# PIC_16F877A_Board_V4_2_SMD.net
KiCad netlist of a schematic drawn in EAGLE
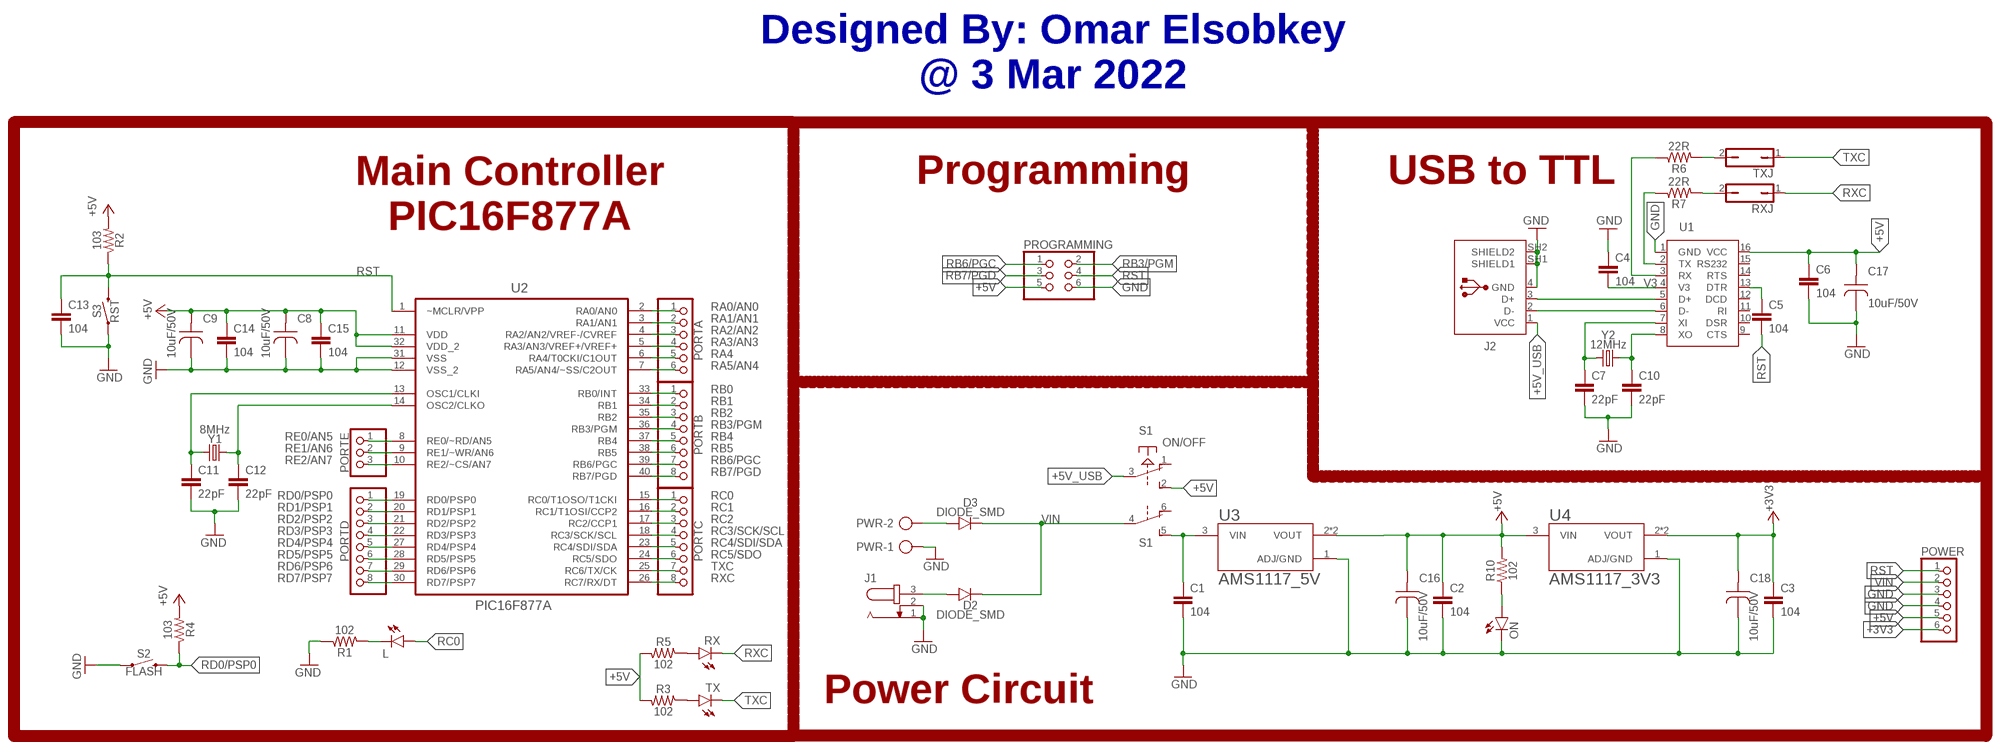
[diagram p0: schematic, sheet 1]

(export (version "E")
  (design (tool "Eeschema 10.0.6"))
  (components
    (comp (ref "C1")
      (value "104")
      (footprint "eagle-import:C0805K")
      (libsource (lib "eagle-import") (part "C-EUC0805K"))
    )
    (comp (ref "C2")
      (value "104")
      (footprint "eagle-import:C0805K")
      (libsource (lib "eagle-import") (part "C-EUC0805K"))
    )
    (comp (ref "C3")
      (value "104")
      (footprint "eagle-import:C0805K")
      (libsource (lib "eagle-import") (part "C-EUC0805K"))
    )
    (comp (ref "C4")
      (value "104")
      (footprint "eagle-import:C0805K")
      (libsource (lib "eagle-import") (part "C-EUC0805K"))
    )
    (comp (ref "C5")
      (value "104")
      (footprint "eagle-import:C0805K")
      (libsource (lib "eagle-import") (part "C-EUC0805K"))
    )
    (comp (ref "C6")
      (value "104")
      (footprint "eagle-import:C0805K")
      (libsource (lib "eagle-import") (part "C-EUC0805K"))
    )
    (comp (ref "C7")
      (value "22pF")
      (footprint "eagle-import:C0805K")
      (libsource (lib "eagle-import") (part "C-EUC0805K"))
    )
    (comp (ref "C8")
      (value "10uF/50V")
      (footprint "eagle-import:D5")
      (libsource (lib "eagle-import") (part "10UF/50V"))
    )
    (comp (ref "C9")
      (value "10uF/50V")
      (footprint "eagle-import:D5")
      (libsource (lib "eagle-import") (part "10UF/50V"))
    )
    (comp (ref "C10")
      (value "22pF")
      (footprint "eagle-import:C0805K")
      (libsource (lib "eagle-import") (part "C-EUC0805K"))
    )
    (comp (ref "C11")
      (value "22pF")
      (footprint "eagle-import:C0805K")
      (libsource (lib "eagle-import") (part "C-EUC0805K"))
    )
    (comp (ref "C12")
      (value "22pF")
      (footprint "eagle-import:C0805K")
      (libsource (lib "eagle-import") (part "C-EUC0805K"))
    )
    (comp (ref "C13")
      (value "104")
      (footprint "eagle-import:C0805K")
      (libsource (lib "eagle-import") (part "C-EUC0805K"))
    )
    (comp (ref "C14")
      (value "104")
      (footprint "eagle-import:C0805K")
      (libsource (lib "eagle-import") (part "C-EUC0805K"))
    )
    (comp (ref "C15")
      (value "104")
      (footprint "eagle-import:C0805K")
      (libsource (lib "eagle-import") (part "C-EUC0805K"))
    )
    (comp (ref "C16")
      (value "10uF/50V")
      (footprint "eagle-import:D5")
      (libsource (lib "eagle-import") (part "10UF/50V"))
    )
    (comp (ref "C17")
      (value "10uF/50V")
      (footprint "eagle-import:D5")
      (libsource (lib "eagle-import") (part "10UF/50V"))
    )
    (comp (ref "C18")
      (value "10uF/50V")
      (footprint "eagle-import:D5")
      (libsource (lib "eagle-import") (part "10UF/50V"))
    )
    (comp (ref "D2")
      (value "DIODE_SMD")
      (footprint "eagle-import:SMA_DO-214AC")
      (fields (field (name "MF") "NKK Switches") (field (name "MP") "S1A"))
      (libsource (lib "eagle-import") (part "DIODE_SMD"))
    )
    (comp (ref "D3")
      (value "DIODE_SMD")
      (footprint "eagle-import:SMA_DO-214AC")
      (fields (field (name "MF") "NKK Switches") (field (name "MP") "S1A"))
      (libsource (lib "eagle-import") (part "DIODE_SMD"))
    )
    (comp (ref "J1")
      (value "JACK-PLUG0")
      (footprint "eagle-import:SPC4077")
      (libsource (lib "eagle-import") (part "JACK-PLUG0"))
    )
    (comp (ref "J2")
      (value "61729-1011")
      (footprint "eagle-import:61729-1011BLF")
      (fields (field (name "MANUFACTURER") "Amphenol ICC (FCI)") (field (name "MPN") "61729-1011BLF"))
      (libsource (lib "eagle-import") (part "61729-1011"))
    )
    (comp (ref "L")
      (value "LEDCHIPLED_1206")
      (footprint "eagle-import:CHIPLED_1206")
      (libsource (lib "eagle-import") (part "LEDCHIPLED_1206"))
    )
    (comp (ref "ON")
      (value "LEDCHIPLED_1206")
      (footprint "eagle-import:CHIPLED_1206")
      (libsource (lib "eagle-import") (part "LEDCHIPLED_1206"))
    )
    (comp (ref "PORTA")
      (value "PINHD-1X6")
      (footprint "eagle-import:1X06")
      (libsource (lib "eagle-import") (part "PINHD-1X6"))
    )
    (comp (ref "PORTB")
      (value "PINHD-1X8")
      (footprint "eagle-import:1X08")
      (libsource (lib "eagle-import") (part "PINHD-1X8"))
    )
    (comp (ref "PORTC")
      (value "PINHD-1X8")
      (footprint "eagle-import:1X08")
      (libsource (lib "eagle-import") (part "PINHD-1X8"))
    )
    (comp (ref "PORTD")
      (value "PINHD-1X8")
      (footprint "eagle-import:1X08")
      (libsource (lib "eagle-import") (part "PINHD-1X8"))
    )
    (comp (ref "PORTE")
      (value "PINHD-1X3")
      (footprint "eagle-import:1X03")
      (libsource (lib "eagle-import") (part "PINHD-1X3"))
    )
    (comp (ref "POWER")
      (value "PINHD-1X6")
      (footprint "eagle-import:1X06")
      (libsource (lib "eagle-import") (part "PINHD-1X6"))
    )
    (comp (ref "PROGRAMMING")
      (value "PINHD-2X3")
      (footprint "eagle-import:2X03")
      (libsource (lib "eagle-import") (part "PINHD-2X3"))
    )
    (comp (ref "PWR") (value "2P") (footprint "eagle-import:2P") (libsource (lib "eagle-import") (part "2P")))
    (comp (ref "R1")
      (value "102")
      (footprint "eagle-import:1206")
      (libsource (lib "eagle-import") (part "RESISTOR1206"))
    )
    (comp (ref "R2")
      (value "103")
      (footprint "eagle-import:1206")
      (libsource (lib "eagle-import") (part "RESISTOR1206"))
    )
    (comp (ref "R3")
      (value "102")
      (footprint "eagle-import:1206")
      (libsource (lib "eagle-import") (part "RESISTOR1206"))
    )
    (comp (ref "R4")
      (value "103")
      (footprint "eagle-import:1206")
      (libsource (lib "eagle-import") (part "RESISTOR1206"))
    )
    (comp (ref "R5")
      (value "102")
      (footprint "eagle-import:1206")
      (libsource (lib "eagle-import") (part "RESISTOR1206"))
    )
    (comp (ref "R6")
      (value "22R")
      (footprint "eagle-import:1206")
      (libsource (lib "eagle-import") (part "RESISTOR1206"))
    )
    (comp (ref "R7")
      (value "22R")
      (footprint "eagle-import:1206")
      (libsource (lib "eagle-import") (part "RESISTOR1206"))
    )
    (comp (ref "R10")
      (value "102")
      (footprint "eagle-import:1206")
      (libsource (lib "eagle-import") (part "RESISTOR1206"))
    )
    (comp (ref "RX")
      (value "LEDCHIPLED_1206")
      (footprint "eagle-import:CHIPLED_1206")
      (libsource (lib "eagle-import") (part "LEDCHIPLED_1206"))
    )
    (comp (ref "RXJ")
      (value "JP1Q")
      (footprint "eagle-import:JP1")
      (libsource (lib "eagle-import") (part "JP1Q"))
    )
    (comp (ref "S1")
      (value "ON/OFF")
      (footprint "eagle-import:PVA2R")
      (libsource (lib "eagle-import") (part "PVA2R"))
    )
    (comp (ref "S2")
      (value "FLASH")
      (footprint "eagle-import:TACTILE_SWITCH_SMD_6.0X3.5MM")
      (libsource (lib "eagle-import") (part "MOMENTARY-SWITCH-SPST-SMD-6.0X3.5MM"))
    )
    (comp (ref "S3")
      (value "RST")
      (footprint "eagle-import:TACTILE_SWITCH_SMD_6.0X3.5MM")
      (libsource (lib "eagle-import") (part "MOMENTARY-SWITCH-SPST-SMD-6.0X3.5MM"))
    )
    (comp (ref "TX")
      (value "LEDCHIPLED_1206")
      (footprint "eagle-import:CHIPLED_1206")
      (libsource (lib "eagle-import") (part "LEDCHIPLED_1206"))
    )
    (comp (ref "TXJ")
      (value "JP1Q")
      (footprint "eagle-import:JP1")
      (libsource (lib "eagle-import") (part "JP1Q"))
    )
    (comp (ref "U1")
      (value "CH340G")
      (footprint "eagle-import:SOP-16")
      (libsource (lib "eagle-import") (part "CH340G"))
    )
    (comp (ref "U2")
      (value "PIC16F877A")
      (footprint "eagle-import:PDIP-40")
      (fields (field (name "MF") "Microchip") (field (name "MP") "PIC16F877A-I/P"))
      (libsource (lib "eagle-import") (part "PIC16F877A-I/P"))
    )
    (comp (ref "U3")
      (value "AMS1117_5V")
      (footprint "eagle-import:SOT223")
      (libsource (lib "eagle-import") (part "AMS1117"))
    )
    (comp (ref "U4")
      (value "AMS1117_3V3")
      (footprint "eagle-import:SOT223")
      (libsource (lib "eagle-import") (part "AMS1117"))
    )
    (comp (ref "Y1")
      (value "8MHz")
      (footprint "eagle-import:HC49U")
      (libsource (lib "eagle-import") (part "CRYSTALPTH-HC49UV"))
    )
    (comp (ref "Y2")
      (value "12MHz")
      (footprint "eagle-import:HC49U")
      (libsource (lib "eagle-import") (part "CRYSTALPTH-HC49UV"))
    )
  )
  (nets
    (net (code "1") (name "+3V3") (class "Default")
      (node (ref "C18") (pin "A") (pinfunction "A_A") (pintype "bidirectional"))
      (node (ref "C3") (pin "1") (pinfunction "1_1") (pintype "passive"))
      (node (ref "POWER") (pin "6") (pinfunction "6_6") (pintype "passive"))
      (node (ref "U4") (pin "2") (pinfunction "VOUT_2") (pintype "output"))
      (node (ref "U4") (pin "4") (pinfunction "VOUT_4") (pintype "output"))
    )
    (net (code "2") (name "+5V") (class "Default")
      (node (ref "C14") (pin "1") (pinfunction "1_1") (pintype "passive"))
      (node (ref "C15") (pin "1") (pinfunction "1_1") (pintype "passive"))
      (node (ref "C16") (pin "A") (pinfunction "A_A") (pintype "bidirectional"))
      (node (ref "C17") (pin "A") (pinfunction "A_A") (pintype "bidirectional"))
      (node (ref "C2") (pin "1") (pinfunction "1_1") (pintype "passive"))
      (node (ref "C6") (pin "1") (pinfunction "1_1") (pintype "passive"))
      (node (ref "C8") (pin "A") (pinfunction "A_A") (pintype "bidirectional"))
      (node (ref "C9") (pin "A") (pinfunction "A_A") (pintype "bidirectional"))
      (node (ref "POWER") (pin "5") (pinfunction "5_5") (pintype "passive"))
      (node (ref "PROGRAMMING") (pin "5") (pinfunction "5_5") (pintype "passive"))
      (node (ref "R10") (pin "2") (pinfunction "2_2") (pintype "passive"))
      (node (ref "R2") (pin "2") (pinfunction "2_2") (pintype "passive"))
      (node (ref "R3") (pin "2") (pinfunction "2_2") (pintype "passive"))
      (node (ref "R4") (pin "2") (pinfunction "2_2") (pintype "passive"))
      (node (ref "R5") (pin "2") (pinfunction "2_2") (pintype "passive"))
      (node (ref "S1") (pin "2") (pinfunction "S_2") (pintype "passive"))
      (node (ref "U1") (pin "16") (pinfunction "VCC_16") (pintype "bidirectional"))
      (node (ref "U2") (pin "11") (pinfunction "VDD_11") (pintype "power_in"))
      (node (ref "U2") (pin "32") (pinfunction "VDD_2_32") (pintype "power_in"))
      (node (ref "U3") (pin "2") (pinfunction "VOUT_2") (pintype "output"))
      (node (ref "U3") (pin "4") (pinfunction "VOUT_4") (pintype "output"))
      (node (ref "U4") (pin "3") (pinfunction "VIN_3") (pintype "input"))
    )
    (net (code "3") (name "+5V_USB") (class "Default")
      (node (ref "J2") (pin "1") (pinfunction "VCC_1") (pintype "power_in"))
      (node (ref "S1") (pin "3") (pinfunction "P_3") (pintype "passive"))
    )
    (net (code "4") (name "/RA0{slash}AN0") (class "Default")
      (node (ref "PORTA") (pin "1") (pinfunction "1_1") (pintype "passive"))
      (node (ref "U2") (pin "2") (pinfunction "RA0/AN0_2") (pintype "bidirectional"))
    )
    (net (code "5") (name "/RA1{slash}AN1") (class "Default")
      (node (ref "PORTA") (pin "2") (pinfunction "2_2") (pintype "passive"))
      (node (ref "U2") (pin "3") (pinfunction "RA1/AN1_3") (pintype "bidirectional"))
    )
    (net (code "6") (name "/RA2{slash}AN2") (class "Default")
      (node (ref "PORTA") (pin "3") (pinfunction "3_3") (pintype "passive"))
      (node (ref "U2") (pin "4") (pinfunction "RA2/AN2/VREF-/CVREF_4") (pintype "bidirectional"))
    )
    (net (code "7") (name "/RA3{slash}AN3") (class "Default")
      (node (ref "PORTA") (pin "4") (pinfunction "4_4") (pintype "passive"))
      (node (ref "U2") (pin "5") (pinfunction "RA3/AN3/VREF+/VREF+_5") (pintype "bidirectional"))
    )
    (net (code "8") (name "/RA4") (class "Default")
      (node (ref "PORTA") (pin "5") (pinfunction "5_5") (pintype "passive"))
      (node (ref "U2") (pin "6") (pinfunction "RA4/T0CKI/C1OUT_6") (pintype "bidirectional"))
    )
    (net (code "9") (name "/RA5{slash}AN4") (class "Default")
      (node (ref "PORTA") (pin "6") (pinfunction "6_6") (pintype "passive"))
      (node (ref "U2") (pin "7") (pinfunction "RA5/AN4/~{SS/C2OUT}_7") (pintype "bidirectional"))
    )
    (net (code "10") (name "/RB0") (class "Default")
      (node (ref "PORTB") (pin "1") (pinfunction "1_1") (pintype "passive"))
      (node (ref "U2") (pin "33") (pinfunction "RB0/INT_33") (pintype "bidirectional"))
    )
    (net (code "11") (name "/RB1") (class "Default")
      (node (ref "PORTB") (pin "2") (pinfunction "2_2") (pintype "passive"))
      (node (ref "U2") (pin "34") (pinfunction "RB1_34") (pintype "bidirectional"))
    )
    (net (code "12") (name "/RB2") (class "Default")
      (node (ref "PORTB") (pin "3") (pinfunction "3_3") (pintype "passive"))
      (node (ref "U2") (pin "35") (pinfunction "RB2_35") (pintype "bidirectional"))
    )
    (net (code "13") (name "/RB4") (class "Default")
      (node (ref "PORTB") (pin "5") (pinfunction "5_5") (pintype "passive"))
      (node (ref "U2") (pin "37") (pinfunction "RB4_37") (pintype "bidirectional"))
    )
    (net (code "14") (name "/RB5") (class "Default")
      (node (ref "PORTB") (pin "6") (pinfunction "6_6") (pintype "passive"))
      (node (ref "U2") (pin "38") (pinfunction "RB5_38") (pintype "bidirectional"))
    )
    (net (code "15") (name "/RC1") (class "Default")
      (node (ref "PORTC") (pin "2") (pinfunction "2_2") (pintype "passive"))
      (node (ref "U2") (pin "16") (pinfunction "RC1/T1OSI/CCP2_16") (pintype "bidirectional"))
    )
    (net (code "16") (name "/RC2") (class "Default")
      (node (ref "PORTC") (pin "3") (pinfunction "3_3") (pintype "passive"))
      (node (ref "U2") (pin "17") (pinfunction "RC2/CCP1_17") (pintype "bidirectional"))
    )
    (net (code "17") (name "/RC3{slash}SCK{slash}SCL") (class "Default")
      (node (ref "PORTC") (pin "4") (pinfunction "4_4") (pintype "passive"))
      (node (ref "U2") (pin "18") (pinfunction "RC3/SCK/SCL_18") (pintype "bidirectional"))
    )
    (net (code "18") (name "/RC4{slash}SDI{slash}SDA") (class "Default")
      (node (ref "PORTC") (pin "5") (pinfunction "5_5") (pintype "passive"))
      (node (ref "U2") (pin "23") (pinfunction "RC4/SDI/SDA_23") (pintype "bidirectional"))
    )
    (net (code "19") (name "/RC5{slash}SDO") (class "Default")
      (node (ref "PORTC") (pin "6") (pinfunction "6_6") (pintype "passive"))
      (node (ref "U2") (pin "24") (pinfunction "RC5/SDO_24") (pintype "bidirectional"))
    )
    (net (code "20") (name "/RD1{slash}PSP1") (class "Default")
      (node (ref "PORTD") (pin "2") (pinfunction "2_2") (pintype "passive"))
      (node (ref "U2") (pin "20") (pinfunction "RD1/PSP1_20") (pintype "bidirectional"))
    )
    (net (code "21") (name "/RD2{slash}PSP2") (class "Default")
      (node (ref "PORTD") (pin "3") (pinfunction "3_3") (pintype "passive"))
      (node (ref "U2") (pin "21") (pinfunction "RD2/PSP2_21") (pintype "bidirectional"))
    )
    (net (code "22") (name "/RD3{slash}PSP3") (class "Default")
      (node (ref "PORTD") (pin "4") (pinfunction "4_4") (pintype "passive"))
      (node (ref "U2") (pin "22") (pinfunction "RD3/PSP3_22") (pintype "bidirectional"))
    )
    (net (code "23") (name "/RD4{slash}PSP4") (class "Default")
      (node (ref "PORTD") (pin "5") (pinfunction "5_5") (pintype "passive"))
      (node (ref "U2") (pin "27") (pinfunction "RD4/PSP4_27") (pintype "bidirectional"))
    )
    (net (code "24") (name "/RD5{slash}PSP5") (class "Default")
      (node (ref "PORTD") (pin "6") (pinfunction "6_6") (pintype "passive"))
      (node (ref "U2") (pin "28") (pinfunction "RD5/PSP5_28") (pintype "bidirectional"))
    )
    (net (code "25") (name "/RD6{slash}PSP6") (class "Default")
      (node (ref "PORTD") (pin "7") (pinfunction "7_7") (pintype "passive"))
      (node (ref "U2") (pin "29") (pinfunction "RD6/PSP6_29") (pintype "bidirectional"))
    )
    (net (code "26") (name "/RD7{slash}PSP7") (class "Default")
      (node (ref "PORTD") (pin "8") (pinfunction "8_8") (pintype "passive"))
      (node (ref "U2") (pin "30") (pinfunction "RD7/PSP7_30") (pintype "bidirectional"))
    )
    (net (code "27") (name "/RE0{slash}AN5") (class "Default")
      (node (ref "PORTE") (pin "1") (pinfunction "1_1") (pintype "passive"))
      (node (ref "U2") (pin "8") (pinfunction "RE0/~{RD/AN5}_8") (pintype "bidirectional"))
    )
    (net (code "28") (name "/RE1{slash}AN6") (class "Default")
      (node (ref "PORTE") (pin "2") (pinfunction "2_2") (pintype "passive"))
      (node (ref "U2") (pin "9") (pinfunction "RE1/~{WR/AN6}_9") (pintype "bidirectional"))
    )
    (net (code "29") (name "/RE2{slash}AN7") (class "Default")
      (node (ref "PORTE") (pin "3") (pinfunction "3_3") (pintype "passive"))
      (node (ref "U2") (pin "10") (pinfunction "RE2/~{CS/AN7}_10") (pintype "bidirectional"))
    )
    (net (code "30") (name "/V3") (class "Default")
      (node (ref "C4") (pin "2") (pinfunction "2_2") (pintype "passive"))
      (node (ref "U1") (pin "4") (pinfunction "V3_4") (pintype "bidirectional"))
    )
    (net (code "31") (name "GND") (class "Default")
      (node (ref "C1") (pin "2") (pinfunction "2_2") (pintype "passive"))
      (node (ref "C10") (pin "2") (pinfunction "2_2") (pintype "passive"))
      (node (ref "C11") (pin "2") (pinfunction "2_2") (pintype "passive"))
      (node (ref "C12") (pin "2") (pinfunction "2_2") (pintype "passive"))
      (node (ref "C13") (pin "2") (pinfunction "2_2") (pintype "passive"))
      (node (ref "C14") (pin "2") (pinfunction "2_2") (pintype "passive"))
      (node (ref "C15") (pin "2") (pinfunction "2_2") (pintype "passive"))
      (node (ref "C16") (pin "K") (pinfunction "K_K") (pintype "bidirectional"))
      (node (ref "C17") (pin "K") (pinfunction "K_K") (pintype "bidirectional"))
      (node (ref "C18") (pin "K") (pinfunction "K_K") (pintype "bidirectional"))
      (node (ref "C2") (pin "2") (pinfunction "2_2") (pintype "passive"))
      (node (ref "C3") (pin "2") (pinfunction "2_2") (pintype "passive"))
      (node (ref "C4") (pin "1") (pinfunction "1_1") (pintype "passive"))
      (node (ref "C6") (pin "2") (pinfunction "2_2") (pintype "passive"))
      (node (ref "C7") (pin "2") (pinfunction "2_2") (pintype "passive"))
      (node (ref "C8") (pin "K") (pinfunction "K_K") (pintype "bidirectional"))
      (node (ref "C9") (pin "K") (pinfunction "K_K") (pintype "bidirectional"))
      (node (ref "J1") (pin "1") (pinfunction "1_1") (pintype "passive"))
      (node (ref "J1") (pin "2") (pinfunction "2_2") (pintype "passive"))
      (node (ref "J2") (pin "4") (pinfunction "GND_4") (pintype "power_in"))
      (node (ref "J2") (pin "SH1") (pinfunction "SHIELD1_SH1") (pintype "power_in"))
      (node (ref "J2") (pin "SH2") (pinfunction "SHIELD2_SH2") (pintype "power_in"))
      (node (ref "ON") (pin "C") (pinfunction "C_C") (pintype "passive"))
      (node (ref "POWER") (pin "3") (pinfunction "3_3") (pintype "passive"))
      (node (ref "POWER") (pin "4") (pinfunction "4_4") (pintype "passive"))
      (node (ref "PROGRAMMING") (pin "6") (pinfunction "6_6") (pintype "passive"))
      (node (ref "PWR") (pin "1") (pinfunction "KL_1") (pintype "passive"))
      (node (ref "R1") (pin "1") (pinfunction "1_1") (pintype "passive"))
      (node (ref "S2") (pin "1") (pinfunction "1_1") (pintype "passive"))
      (node (ref "S3") (pin "1") (pinfunction "1_1") (pintype "passive"))
      (node (ref "U1") (pin "1") (pinfunction "GND_1") (pintype "bidirectional"))
      (node (ref "U2") (pin "12") (pinfunction "VSS_2_12") (pintype "power_in"))
      (node (ref "U2") (pin "31") (pinfunction "VSS_31") (pintype "power_in"))
      (node (ref "U3") (pin "1") (pinfunction "ADJ/GND_1") (pintype "power_in"))
      (node (ref "U4") (pin "1") (pinfunction "ADJ/GND_1") (pintype "power_in"))
    )
    (net (code "32") (name "Net-(D2-A)") (class "Default")
      (node (ref "D2") (pin "2") (pinfunction "A_2") (pintype "passive"))
      (node (ref "J1") (pin "3") (pinfunction "3_3") (pintype "passive"))
    )
    (net (code "33") (name "Net-(D3-A)") (class "Default")
      (node (ref "D3") (pin "2") (pinfunction "A_2") (pintype "passive"))
      (node (ref "PWR") (pin "2") (pinfunction "KL_2") (pintype "passive"))
    )
    (net (code "34") (name "Net-(J2-D+)") (class "Default")
      (node (ref "J2") (pin "3") (pinfunction "D+_3") (pintype "bidirectional"))
      (node (ref "U1") (pin "5") (pinfunction "D+_5") (pintype "bidirectional"))
    )
    (net (code "35") (name "Net-(J2-D-)") (class "Default")
      (node (ref "J2") (pin "2") (pinfunction "D-_2") (pintype "bidirectional"))
      (node (ref "U1") (pin "6") (pinfunction "D-_6") (pintype "bidirectional"))
    )
    (net (code "36") (name "Net-(L-PadC)") (class "Default")
      (node (ref "L") (pin "C") (pinfunction "C_C") (pintype "passive"))
      (node (ref "R1") (pin "2") (pinfunction "2_2") (pintype "passive"))
    )
    (net (code "37") (name "Net-(ON-PadA)") (class "Default")
      (node (ref "ON") (pin "A") (pinfunction "A_A") (pintype "passive"))
      (node (ref "R10") (pin "1") (pinfunction "1_1") (pintype "passive"))
    )
    (net (code "38") (name "Net-(R3-Pad1)") (class "Default")
      (node (ref "R3") (pin "1") (pinfunction "1_1") (pintype "passive"))
      (node (ref "TX") (pin "A") (pinfunction "A_A") (pintype "passive"))
    )
    (net (code "39") (name "Net-(R5-Pad1)") (class "Default")
      (node (ref "R5") (pin "1") (pinfunction "1_1") (pintype "passive"))
      (node (ref "RX") (pin "A") (pinfunction "A_A") (pintype "passive"))
    )
    (net (code "40") (name "Net-(R6-Pad2)") (class "Default")
      (node (ref "R6") (pin "2") (pinfunction "2_2") (pintype "passive"))
      (node (ref "TXJ") (pin "2") (pinfunction "2_2") (pintype "passive"))
    )
    (net (code "41") (name "Net-(R7-Pad2)") (class "Default")
      (node (ref "R7") (pin "2") (pinfunction "2_2") (pintype "passive"))
      (node (ref "RXJ") (pin "2") (pinfunction "2_2") (pintype "passive"))
    )
    (net (code "42") (name "Net-(S1B-S)") (class "Default")
      (node (ref "C1") (pin "1") (pinfunction "1_1") (pintype "passive"))
      (node (ref "S1") (pin "5") (pinfunction "S_5") (pintype "passive"))
      (node (ref "U3") (pin "3") (pinfunction "VIN_3") (pintype "input"))
    )
    (net (code "43") (name "Net-(U1-DTR)") (class "Default")
      (node (ref "C5") (pin "1") (pinfunction "1_1") (pintype "passive"))
      (node (ref "U1") (pin "13") (pinfunction "DTR_13") (pintype "bidirectional"))
    )
    (net (code "44") (name "Net-(U1-RX)") (class "Default")
      (node (ref "R6") (pin "1") (pinfunction "1_1") (pintype "passive"))
      (node (ref "U1") (pin "3") (pinfunction "RX_3") (pintype "bidirectional"))
    )
    (net (code "45") (name "Net-(U1-TX)") (class "Default")
      (node (ref "R7") (pin "1") (pinfunction "1_1") (pintype "passive"))
      (node (ref "U1") (pin "2") (pinfunction "TX_2") (pintype "bidirectional"))
    )
    (net (code "46") (name "Net-(U1-XI)") (class "Default")
      (node (ref "C7") (pin "1") (pinfunction "1_1") (pintype "passive"))
      (node (ref "U1") (pin "7") (pinfunction "XI_7") (pintype "bidirectional"))
      (node (ref "Y2") (pin "2") (pinfunction "2_2") (pintype "passive"))
    )
    (net (code "47") (name "Net-(U1-XO)") (class "Default")
      (node (ref "C10") (pin "1") (pinfunction "1_1") (pintype "passive"))
      (node (ref "U1") (pin "8") (pinfunction "XO_8") (pintype "bidirectional"))
      (node (ref "Y2") (pin "1") (pinfunction "1_1") (pintype "passive"))
    )
    (net (code "48") (name "Net-(U2-OSC1{slash}CLKI)") (class "Default")
      (node (ref "C11") (pin "1") (pinfunction "1_1") (pintype "passive"))
      (node (ref "U2") (pin "13") (pinfunction "OSC1/CLKI_13") (pintype "input"))
      (node (ref "Y1") (pin "2") (pinfunction "2_2") (pintype "passive"))
    )
    (net (code "49") (name "Net-(U2-OSC2{slash}CLKO)") (class "Default")
      (node (ref "C12") (pin "1") (pinfunction "1_1") (pintype "passive"))
      (node (ref "U2") (pin "14") (pinfunction "OSC2/CLKO_14") (pintype "output"))
      (node (ref "Y1") (pin "1") (pinfunction "1_1") (pintype "passive"))
    )
    (net (code "50") (name "RB3{slash}PGM") (class "Default")
      (node (ref "PORTB") (pin "4") (pinfunction "4_4") (pintype "passive"))
      (node (ref "PROGRAMMING") (pin "2") (pinfunction "2_2") (pintype "passive"))
      (node (ref "U2") (pin "36") (pinfunction "RB3/PGM_36") (pintype "bidirectional"))
    )
    (net (code "51") (name "RB6{slash}PGC") (class "Default")
      (node (ref "PORTB") (pin "7") (pinfunction "7_7") (pintype "passive"))
      (node (ref "PROGRAMMING") (pin "1") (pinfunction "1_1") (pintype "passive"))
      (node (ref "U2") (pin "39") (pinfunction "RB6/PGC_39") (pintype "bidirectional"))
    )
    (net (code "52") (name "RB7{slash}PGD") (class "Default")
      (node (ref "PORTB") (pin "8") (pinfunction "8_8") (pintype "passive"))
      (node (ref "PROGRAMMING") (pin "3") (pinfunction "3_3") (pintype "passive"))
      (node (ref "U2") (pin "40") (pinfunction "RB7/PGD_40") (pintype "bidirectional"))
    )
    (net (code "53") (name "RC0") (class "Default")
      (node (ref "L") (pin "A") (pinfunction "A_A") (pintype "passive"))
      (node (ref "PORTC") (pin "1") (pinfunction "1_1") (pintype "passive"))
      (node (ref "U2") (pin "15") (pinfunction "RC0/T1OSO/T1CKI_15") (pintype "bidirectional"))
    )
    (net (code "54") (name "RD0{slash}PSP0") (class "Default")
      (node (ref "PORTD") (pin "1") (pinfunction "1_1") (pintype "passive"))
      (node (ref "R4") (pin "1") (pinfunction "1_1") (pintype "passive"))
      (node (ref "S2") (pin "2") (pinfunction "2_2") (pintype "passive"))
      (node (ref "U2") (pin "19") (pinfunction "RD0/PSP0_19") (pintype "bidirectional"))
    )
    (net (code "55") (name "RST") (class "Default")
      (node (ref "C13") (pin "1") (pinfunction "1_1") (pintype "passive"))
      (node (ref "C5") (pin "2") (pinfunction "2_2") (pintype "passive"))
      (node (ref "POWER") (pin "1") (pinfunction "1_1") (pintype "passive"))
      (node (ref "PROGRAMMING") (pin "4") (pinfunction "4_4") (pintype "passive"))
      (node (ref "R2") (pin "1") (pinfunction "1_1") (pintype "passive"))
      (node (ref "S3") (pin "2") (pinfunction "2_2") (pintype "passive"))
      (node (ref "U2") (pin "1") (pinfunction "~{MCLR/VPP}_1") (pintype "input"))
    )
    (net (code "56") (name "RXC") (class "Default")
      (node (ref "PORTC") (pin "8") (pinfunction "8_8") (pintype "passive"))
      (node (ref "RX") (pin "C") (pinfunction "C_C") (pintype "passive"))
      (node (ref "RXJ") (pin "1") (pinfunction "1_1") (pintype "passive"))
      (node (ref "U2") (pin "26") (pinfunction "RC7/RX/DT_26") (pintype "bidirectional"))
    )
    (net (code "57") (name "TXC") (class "Default")
      (node (ref "PORTC") (pin "7") (pinfunction "7_7") (pintype "passive"))
      (node (ref "TX") (pin "C") (pinfunction "C_C") (pintype "passive"))
      (node (ref "TXJ") (pin "1") (pinfunction "1_1") (pintype "passive"))
      (node (ref "U2") (pin "25") (pinfunction "RC6/TX/CK_25") (pintype "bidirectional"))
    )
    (net (code "58") (name "VIN") (class "Default")
      (node (ref "D2") (pin "1") (pinfunction "C_1") (pintype "passive"))
      (node (ref "D3") (pin "1") (pinfunction "C_1") (pintype "passive"))
      (node (ref "POWER") (pin "2") (pinfunction "2_2") (pintype "passive"))
      (node (ref "S1") (pin "4") (pinfunction "P_4") (pintype "passive"))
    )
    (net (code "59") (name "unconnected-(S1A-O-Pad1)") (class "Default")
      (node (ref "S1") (pin "1") (pinfunction "O_1") (pintype "passive"))
    )
    (net (code "60") (name "unconnected-(S1B-O-Pad6)") (class "Default")
      (node (ref "S1") (pin "6") (pinfunction "O_6") (pintype "passive"))
    )
    (net (code "61") (name "unconnected-(U1-CTS-Pad9)") (class "Default")
      (node (ref "U1") (pin "9") (pinfunction "CTS_9") (pintype "bidirectional"))
    )
    (net (code "62") (name "unconnected-(U1-DCD-Pad12)") (class "Default")
      (node (ref "U1") (pin "12") (pinfunction "DCD_12") (pintype "bidirectional"))
    )
    (net (code "63") (name "unconnected-(U1-DSR-Pad10)") (class "Default")
      (node (ref "U1") (pin "10") (pinfunction "DSR_10") (pintype "bidirectional"))
    )
    (net (code "64") (name "unconnected-(U1-RI-Pad11)") (class "Default")
      (node (ref "U1") (pin "11") (pinfunction "RI_11") (pintype "bidirectional"))
    )
    (net (code "65") (name "unconnected-(U1-RS232-Pad15)") (class "Default")
      (node (ref "U1") (pin "15") (pinfunction "RS232_15") (pintype "bidirectional"))
    )
    (net (code "66") (name "unconnected-(U1-RTS-Pad14)") (class "Default")
      (node (ref "U1") (pin "14") (pinfunction "RTS_14") (pintype "bidirectional"))
    )
  )
)
